# main-board-rev1d.net
KiCad netlist of a schematic drawn in EAGLE
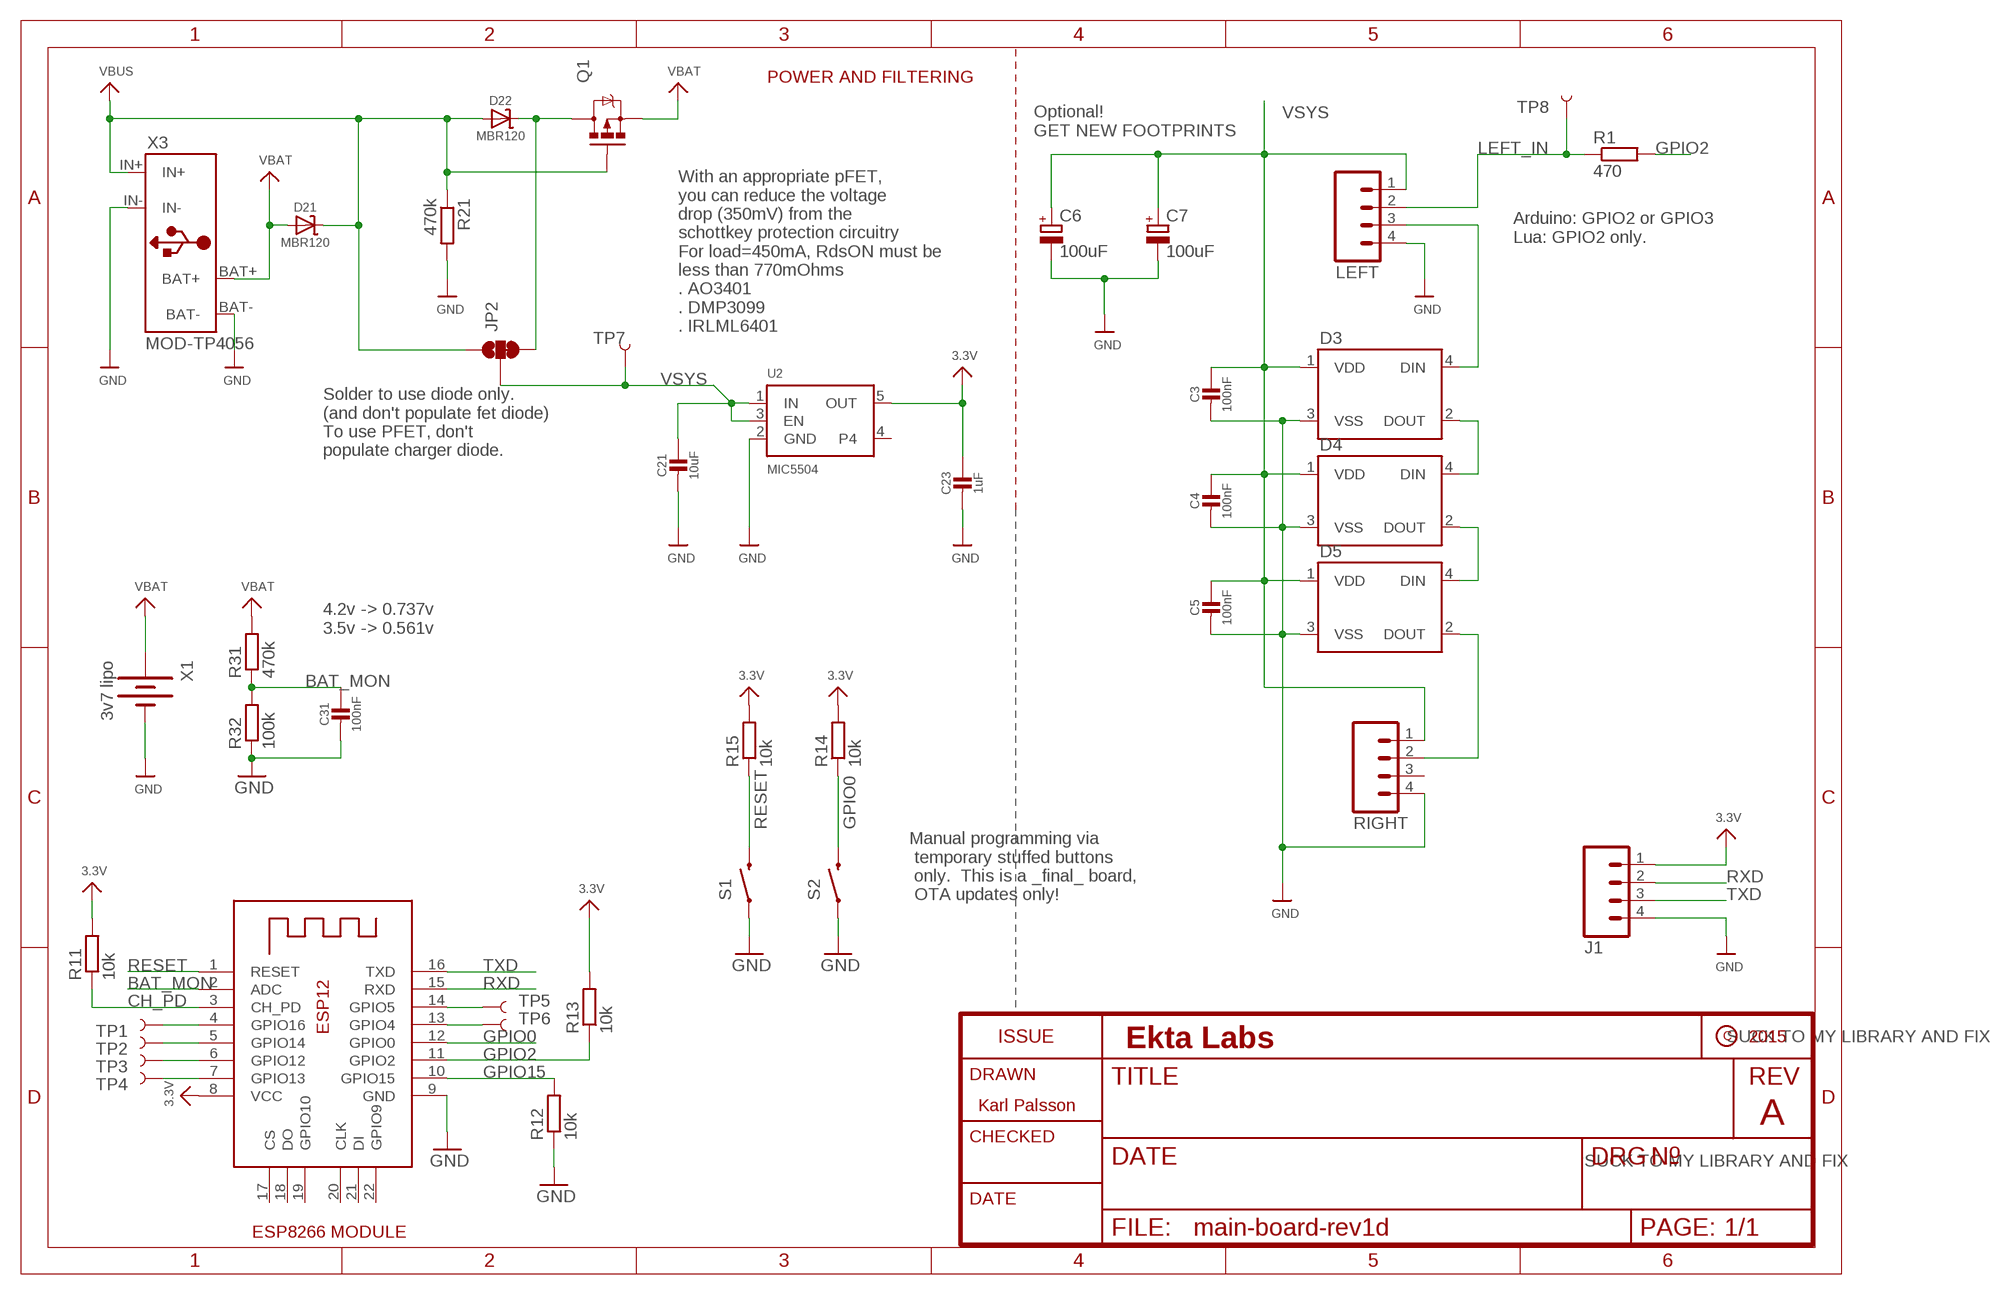
[diagram p0: schematic, sheet 1]

(export (version "E")
  (design (tool "Eeschema 10.0.6"))
  (components
    (comp (ref "C3")
      (value "100nF")
      (footprint "eagle-import:0805-NO")
      (libsource (lib "eagle-import") (part "CAP_CERAMIC0805-NOOUTLINE"))
    )
    (comp (ref "C4")
      (value "100nF")
      (footprint "eagle-import:0805-NO")
      (libsource (lib "eagle-import") (part "CAP_CERAMIC0805-NOOUTLINE"))
    )
    (comp (ref "C5")
      (value "100nF")
      (footprint "eagle-import:0805-NO")
      (libsource (lib "eagle-import") (part "CAP_CERAMIC0805-NOOUTLINE"))
    )
    (comp (ref "C6")
      (value "100uF")
      (footprint "eagle-import:PANASONIC_B")
      (libsource (lib "eagle-import") (part "CPOL-EUB"))
    )
    (comp (ref "C7")
      (value "100uF")
      (footprint "eagle-import:PANASONIC_B")
      (libsource (lib "eagle-import") (part "CPOL-EUB"))
    )
    (comp (ref "C21")
      (value "10uF")
      (footprint "eagle-import:0805-NO")
      (libsource (lib "eagle-import") (part "CAP_CERAMIC0805-NOOUTLINE"))
    )
    (comp (ref "C23")
      (value "1uF")
      (footprint "eagle-import:0805-NO")
      (libsource (lib "eagle-import") (part "CAP_CERAMIC0805-NOOUTLINE"))
    )
    (comp (ref "C31")
      (value "100nF")
      (footprint "eagle-import:0805-NO")
      (libsource (lib "eagle-import") (part "CAP_CERAMIC0805-NOOUTLINE"))
    )
    (comp (ref "D3")
      (value "WS2812B")
      (footprint "eagle-import:WS2812B")
      (libsource (lib "eagle-import") (part "WS2812B"))
    )
    (comp (ref "D4")
      (value "WS2812B")
      (footprint "eagle-import:WS2812B")
      (libsource (lib "eagle-import") (part "WS2812B"))
    )
    (comp (ref "D5")
      (value "WS2812B")
      (footprint "eagle-import:WS2812B")
      (libsource (lib "eagle-import") (part "WS2812B"))
    )
    (comp (ref "D21")
      (value "MBR120")
      (footprint "eagle-import:SOD-123")
      (libsource (lib "eagle-import") (part "DIODE-SCHOTTKYSOD-123"))
    )
    (comp (ref "D22")
      (value "MBR120")
      (footprint "eagle-import:SOD-123")
      (libsource (lib "eagle-import") (part "DIODE-SCHOTTKYSOD-123"))
    )
    (comp (ref "J1")
      (value "M041X04_NO_SILK")
      (footprint "eagle-import:1X04_NO_SILK")
      (libsource (lib "eagle-import") (part "M041X04_NO_SILK"))
    )
    (comp (ref "JP2")
      (value "JUMPER-PAD-3-2OF3_NC_BY_TRACE_LARGE")
      (footprint "eagle-import:PAD-JUMPER-3-2OF3_NC_BY_TRACE_YES_SILK_LARGE")
      (libsource (lib "eagle-import") (part "JUMPER-PAD-3-2OF3_NC_BY_TRACE_LARGE"))
    )
    (comp (ref "LEFT")
      (value "M041X04_NO_SILK")
      (footprint "eagle-import:1X04_NO_SILK")
      (libsource (lib "eagle-import") (part "M041X04_NO_SILK"))
    )
    (comp (ref "Q1")
      (value "MOSFET-PCHANNEL")
      (footprint "eagle-import:SOT23-3")
      (libsource (lib "eagle-import") (part "MOSFET-PCHANNEL"))
    )
    (comp (ref "R1")
      (value "470")
      (footprint "eagle-import:R0603")
      (libsource (lib "eagle-import") (part "R-EU_R0603"))
    )
    (comp (ref "R11")
      (value "10k")
      (footprint "eagle-import:R0603")
      (libsource (lib "eagle-import") (part "R-EU_R0603"))
    )
    (comp (ref "R12")
      (value "10k")
      (footprint "eagle-import:R0603")
      (libsource (lib "eagle-import") (part "R-EU_R0603"))
    )
    (comp (ref "R13")
      (value "10k")
      (footprint "eagle-import:R0603")
      (libsource (lib "eagle-import") (part "R-EU_R0603"))
    )
    (comp (ref "R14")
      (value "10k")
      (footprint "eagle-import:R0603")
      (libsource (lib "eagle-import") (part "R-EU_R0603"))
    )
    (comp (ref "R15")
      (value "10k")
      (footprint "eagle-import:R0603")
      (libsource (lib "eagle-import") (part "R-EU_R0603"))
    )
    (comp (ref "R21")
      (value "470k")
      (footprint "eagle-import:R0603")
      (libsource (lib "eagle-import") (part "R-EU_R0603"))
    )
    (comp (ref "R31")
      (value "470k")
      (footprint "eagle-import:R0603")
      (libsource (lib "eagle-import") (part "R-EU_R0603"))
    )
    (comp (ref "R32")
      (value "100k")
      (footprint "eagle-import:R0603")
      (libsource (lib "eagle-import") (part "R-EU_R0603"))
    )
    (comp (ref "RIGHT")
      (value "M041X04_NO_SILK")
      (footprint "eagle-import:1X04_NO_SILK")
      (libsource (lib "eagle-import") (part "M041X04_NO_SILK"))
    )
    (comp (ref "S1")
      (value "SWITCH-MOMENTARY-2PTH")
      (footprint "eagle-import:TACTILE-PTH")
      (libsource (lib "eagle-import") (part "SWITCH-MOMENTARY-2PTH"))
    )
    (comp (ref "S2")
      (value "SWITCH-MOMENTARY-2PTH")
      (footprint "eagle-import:TACTILE-PTH")
      (libsource (lib "eagle-import") (part "SWITCH-MOMENTARY-2PTH"))
    )
    (comp (ref "TP1")
      (value "TEST-POINTTP_06_TH")
      (footprint "eagle-import:TP_06TH")
      (libsource (lib "eagle-import") (part "TEST-POINTTP_06_TH"))
    )
    (comp (ref "TP2")
      (value "TEST-POINTTP_06_TH")
      (footprint "eagle-import:TP_06TH")
      (libsource (lib "eagle-import") (part "TEST-POINTTP_06_TH"))
    )
    (comp (ref "TP3")
      (value "TEST-POINTTP_06_TH")
      (footprint "eagle-import:TP_06TH")
      (libsource (lib "eagle-import") (part "TEST-POINTTP_06_TH"))
    )
    (comp (ref "TP4")
      (value "TEST-POINTTP_06_TH")
      (footprint "eagle-import:TP_06TH")
      (libsource (lib "eagle-import") (part "TEST-POINTTP_06_TH"))
    )
    (comp (ref "TP5")
      (value "TEST-POINTTP_06_TH")
      (footprint "eagle-import:TP_06TH")
      (libsource (lib "eagle-import") (part "TEST-POINTTP_06_TH"))
    )
    (comp (ref "TP6")
      (value "TEST-POINTTP_06_TH")
      (footprint "eagle-import:TP_06TH")
      (libsource (lib "eagle-import") (part "TEST-POINTTP_06_TH"))
    )
    (comp (ref "TP7")
      (value "TEST-POINTTP_06_TH")
      (footprint "eagle-import:TP_06TH")
      (libsource (lib "eagle-import") (part "TEST-POINTTP_06_TH"))
    )
    (comp (ref "TP8")
      (value "TEST-POINTTP_06_TH")
      (footprint "eagle-import:TP_06TH")
      (libsource (lib "eagle-import") (part "TEST-POINTTP_06_TH"))
    )
    (comp (ref "U2")
      (value "MIC5504")
      (footprint "eagle-import:SOT23-5")
      (libsource (lib "eagle-import") (part "VREG_SOT23-5"))
    )
    (comp (ref "X1")
      (value "3v7 lipo")
      (footprint "eagle-import:BATT-18650-BLOSSOM-1")
      (libsource (lib "eagle-import") (part "BATTERY18650-BLOSSOM"))
    )
    (comp (ref "X2")
      (value "ESP-12")
      (footprint "eagle-import:ESP-12E")
      (libsource (lib "eagle-import") (part "ESP-12E"))
    )
    (comp (ref "X3")
      (value "MOD-TP4056")
      (footprint "eagle-import:MOD-LIPO_CHARGER")
      (libsource (lib "eagle-import") (part "MOD-LIPO_CHARGER"))
    )
  )
  (nets
    (net (code "1") (name "/BAT_MON") (class "Default")
      (node (ref "C31") (pin "1") (pinfunction "1_1") (pintype "passive"))
      (node (ref "R31") (pin "1") (pinfunction "1_1") (pintype "passive"))
      (node (ref "R32") (pin "2") (pinfunction "2_2") (pintype "passive"))
      (node (ref "X2") (pin "2") (pinfunction "ADC_2") (pintype "passive"))
    )
    (net (code "2") (name "/CH_PD") (class "Default")
      (node (ref "R11") (pin "1") (pinfunction "1_1") (pintype "passive"))
      (node (ref "X2") (pin "3") (pinfunction "CH_PD_3") (pintype "input"))
    )
    (net (code "3") (name "/GPIO0") (class "Default")
      (node (ref "R14") (pin "1") (pinfunction "1_1") (pintype "passive"))
      (node (ref "S2") (pin "3") (pinfunction "2_3") (pintype "passive"))
      (node (ref "X2") (pin "12") (pinfunction "GPIO0_12") (pintype "bidirectional"))
    )
    (net (code "4") (name "/GPIO2") (class "Default")
      (node (ref "R1") (pin "2") (pinfunction "2_2") (pintype "passive"))
      (node (ref "R13") (pin "1") (pinfunction "1_1") (pintype "passive"))
      (node (ref "X2") (pin "11") (pinfunction "GPIO2_11") (pintype "bidirectional"))
    )
    (net (code "5") (name "/GPIO15") (class "Default")
      (node (ref "R12") (pin "2") (pinfunction "2_2") (pintype "passive"))
      (node (ref "X2") (pin "10") (pinfunction "GPIO15_10") (pintype "bidirectional"))
    )
    (net (code "6") (name "/LEFT_IN") (class "Default")
      (node (ref "LEFT") (pin "2") (pinfunction "2_2") (pintype "passive"))
      (node (ref "R1") (pin "1") (pinfunction "1_1") (pintype "passive"))
      (node (ref "TP8") (pin "P$1") (pinfunction "1_P$1") (pintype "bidirectional"))
    )
    (net (code "7") (name "/RESET") (class "Default")
      (node (ref "R15") (pin "1") (pinfunction "1_1") (pintype "passive"))
      (node (ref "S1") (pin "3") (pinfunction "2_3") (pintype "passive"))
      (node (ref "X2") (pin "1") (pinfunction "RESET_1") (pintype "input"))
    )
    (net (code "8") (name "/RXD") (class "Default")
      (node (ref "J1") (pin "2") (pinfunction "2_2") (pintype "passive"))
      (node (ref "X2") (pin "15") (pinfunction "RXD_15") (pintype "input"))
    )
    (net (code "9") (name "/TXD") (class "Default")
      (node (ref "J1") (pin "3") (pinfunction "3_3") (pintype "passive"))
      (node (ref "X2") (pin "16") (pinfunction "TXD_16") (pintype "output"))
    )
    (net (code "10") (name "/VSYS") (class "Default")
      (node (ref "C21") (pin "1") (pinfunction "1_1") (pintype "passive"))
      (node (ref "C3") (pin "1") (pinfunction "1_1") (pintype "passive"))
      (node (ref "C4") (pin "1") (pinfunction "1_1") (pintype "passive"))
      (node (ref "C5") (pin "1") (pinfunction "1_1") (pintype "passive"))
      (node (ref "C6") (pin "+") (pinfunction "+_+") (pintype "passive"))
      (node (ref "C7") (pin "+") (pinfunction "+_+") (pintype "passive"))
      (node (ref "D3") (pin "1") (pinfunction "VDD_1") (pintype "power_in"))
      (node (ref "D4") (pin "1") (pinfunction "VDD_1") (pintype "power_in"))
      (node (ref "D5") (pin "1") (pinfunction "VDD_1") (pintype "power_in"))
      (node (ref "JP2") (pin "2") (pinfunction "2_2") (pintype "passive"))
      (node (ref "LEFT") (pin "1") (pinfunction "1_1") (pintype "passive"))
      (node (ref "RIGHT") (pin "1") (pinfunction "1_1") (pintype "passive"))
      (node (ref "TP7") (pin "P$1") (pinfunction "1_P$1") (pintype "bidirectional"))
      (node (ref "U2") (pin "1") (pinfunction "IN_1") (pintype "power_in"))
      (node (ref "U2") (pin "3") (pinfunction "EN_3") (pintype "input"))
    )
    (net (code "11") (name "3.3V") (class "Default")
      (node (ref "C23") (pin "1") (pinfunction "1_1") (pintype "passive"))
      (node (ref "J1") (pin "1") (pinfunction "1_1") (pintype "passive"))
      (node (ref "R11") (pin "2") (pinfunction "2_2") (pintype "passive"))
      (node (ref "R13") (pin "2") (pinfunction "2_2") (pintype "passive"))
      (node (ref "R14") (pin "2") (pinfunction "2_2") (pintype "passive"))
      (node (ref "R15") (pin "2") (pinfunction "2_2") (pintype "passive"))
      (node (ref "U2") (pin "5") (pinfunction "OUT_5") (pintype "power_in"))
      (node (ref "X2") (pin "8") (pinfunction "VCC_8") (pintype "power_in"))
    )
    (net (code "12") (name "GND") (class "Default")
      (node (ref "C21") (pin "2") (pinfunction "2_2") (pintype "passive"))
      (node (ref "C23") (pin "2") (pinfunction "2_2") (pintype "passive"))
      (node (ref "C3") (pin "2") (pinfunction "2_2") (pintype "passive"))
      (node (ref "C31") (pin "2") (pinfunction "2_2") (pintype "passive"))
      (node (ref "C4") (pin "2") (pinfunction "2_2") (pintype "passive"))
      (node (ref "C5") (pin "2") (pinfunction "2_2") (pintype "passive"))
      (node (ref "C6") (pin "-") (pinfunction "-_-") (pintype "passive"))
      (node (ref "C7") (pin "-") (pinfunction "-_-") (pintype "passive"))
      (node (ref "D3") (pin "3") (pinfunction "VSS_3") (pintype "power_in"))
      (node (ref "D4") (pin "3") (pinfunction "VSS_3") (pintype "power_in"))
      (node (ref "D5") (pin "3") (pinfunction "VSS_3") (pintype "power_in"))
      (node (ref "J1") (pin "4") (pinfunction "4_4") (pintype "passive"))
      (node (ref "LEFT") (pin "4") (pinfunction "4_4") (pintype "passive"))
      (node (ref "R12") (pin "1") (pinfunction "1_1") (pintype "passive"))
      (node (ref "R21") (pin "2") (pinfunction "2_2") (pintype "passive"))
      (node (ref "R32") (pin "1") (pinfunction "1_1") (pintype "passive"))
      (node (ref "RIGHT") (pin "4") (pinfunction "4_4") (pintype "passive"))
      (node (ref "S1") (pin "1") (pinfunction "1_1") (pintype "passive"))
      (node (ref "S2") (pin "1") (pinfunction "1_1") (pintype "passive"))
      (node (ref "U2") (pin "2") (pinfunction "GND_2") (pintype "power_in"))
      (node (ref "X1") (pin "-") (pinfunction "-_-") (pintype "power_in"))
      (node (ref "X2") (pin "9") (pinfunction "GND_9") (pintype "power_in"))
      (node (ref "X3") (pin "BAT-") (pinfunction "BAT-_BAT-") (pintype "bidirectional"))
      (node (ref "X3") (pin "IN-") (pinfunction "IN-_IN-") (pintype "bidirectional"))
    )
    (net (code "13") (name "Net-(D3-DIN)") (class "Default")
      (node (ref "D3") (pin "4") (pinfunction "DIN_4") (pintype "input"))
      (node (ref "LEFT") (pin "3") (pinfunction "3_3") (pintype "passive"))
    )
    (net (code "14") (name "Net-(D3-DOUT)") (class "Default")
      (node (ref "D3") (pin "2") (pinfunction "DOUT_2") (pintype "output"))
      (node (ref "D4") (pin "4") (pinfunction "DIN_4") (pintype "input"))
    )
    (net (code "15") (name "Net-(D4-DOUT)") (class "Default")
      (node (ref "D4") (pin "2") (pinfunction "DOUT_2") (pintype "output"))
      (node (ref "D5") (pin "4") (pinfunction "DIN_4") (pintype "input"))
    )
    (net (code "16") (name "Net-(D5-DOUT)") (class "Default")
      (node (ref "D5") (pin "2") (pinfunction "DOUT_2") (pintype "output"))
      (node (ref "RIGHT") (pin "2") (pinfunction "2_2") (pintype "passive"))
    )
    (net (code "17") (name "Net-(Q1-D)") (class "Default")
      (node (ref "D22") (pin "C") (pinfunction "C_C") (pintype "passive"))
      (node (ref "JP2") (pin "3") (pinfunction "3_3") (pintype "passive"))
      (node (ref "Q1") (pin "3") (pinfunction "D_3") (pintype "passive"))
    )
    (net (code "18") (name "Net-(TP1-1)") (class "Default")
      (node (ref "TP1") (pin "P$1") (pinfunction "1_P$1") (pintype "bidirectional"))
      (node (ref "X2") (pin "4") (pinfunction "GPIO16_4") (pintype "bidirectional"))
    )
    (net (code "19") (name "Net-(TP2-1)") (class "Default")
      (node (ref "TP2") (pin "P$1") (pinfunction "1_P$1") (pintype "bidirectional"))
      (node (ref "X2") (pin "5") (pinfunction "GPIO14_5") (pintype "bidirectional"))
    )
    (net (code "20") (name "Net-(TP3-1)") (class "Default")
      (node (ref "TP3") (pin "P$1") (pinfunction "1_P$1") (pintype "bidirectional"))
      (node (ref "X2") (pin "6") (pinfunction "GPIO12_6") (pintype "bidirectional"))
    )
    (net (code "21") (name "Net-(TP4-1)") (class "Default")
      (node (ref "TP4") (pin "P$1") (pinfunction "1_P$1") (pintype "bidirectional"))
      (node (ref "X2") (pin "7") (pinfunction "GPIO13_7") (pintype "bidirectional"))
    )
    (net (code "22") (name "Net-(TP5-1)") (class "Default")
      (node (ref "TP5") (pin "P$1") (pinfunction "1_P$1") (pintype "bidirectional"))
      (node (ref "X2") (pin "14") (pinfunction "GPIO5_14") (pintype "bidirectional"))
    )
    (net (code "23") (name "Net-(TP6-1)") (class "Default")
      (node (ref "TP6") (pin "P$1") (pinfunction "1_P$1") (pintype "bidirectional"))
      (node (ref "X2") (pin "13") (pinfunction "GPIO4_13") (pintype "bidirectional"))
    )
    (net (code "24") (name "VBAT") (class "Default")
      (node (ref "D21") (pin "A") (pinfunction "A_A") (pintype "passive"))
      (node (ref "Q1") (pin "2") (pinfunction "S_2") (pintype "passive"))
      (node (ref "R31") (pin "2") (pinfunction "2_2") (pintype "passive"))
      (node (ref "X1") (pin "+") (pinfunction "+_+") (pintype "power_in"))
      (node (ref "X3") (pin "BAT+") (pinfunction "BAT+_BAT+") (pintype "bidirectional"))
    )
    (net (code "25") (name "VBUS") (class "Default")
      (node (ref "D21") (pin "C") (pinfunction "C_C") (pintype "passive"))
      (node (ref "D22") (pin "A") (pinfunction "A_A") (pintype "passive"))
      (node (ref "JP2") (pin "1") (pinfunction "1_1") (pintype "passive"))
      (node (ref "Q1") (pin "1") (pinfunction "G_1") (pintype "passive"))
      (node (ref "R21") (pin "1") (pinfunction "1_1") (pintype "passive"))
      (node (ref "X3") (pin "IN+") (pinfunction "IN+_IN+") (pintype "bidirectional"))
    )
    (net (code "26") (name "unconnected-(RIGHT-Pad3)") (class "Default")
      (node (ref "RIGHT") (pin "3") (pinfunction "3_3") (pintype "passive"))
    )
    (net (code "27") (name "unconnected-(U2-P4-Pad4)") (class "Default")
      (node (ref "U2") (pin "4") (pinfunction "P4_4") (pintype "bidirectional"))
    )
    (net (code "28") (name "unconnected-(X2-CLK-Pad20)") (class "Default")
      (node (ref "X2") (pin "20") (pinfunction "CLK_20") (pintype "bidirectional"))
    )
    (net (code "29") (name "unconnected-(X2-CS-Pad17)") (class "Default")
      (node (ref "X2") (pin "17") (pinfunction "CS_17") (pintype "bidirectional"))
    )
    (net (code "30") (name "unconnected-(X2-DI-Pad21)") (class "Default")
      (node (ref "X2") (pin "21") (pinfunction "DI_21") (pintype "bidirectional"))
    )
    (net (code "31") (name "unconnected-(X2-DO-Pad18)") (class "Default")
      (node (ref "X2") (pin "18") (pinfunction "DO_18") (pintype "bidirectional"))
    )
    (net (code "32") (name "unconnected-(X2-GPIO9-Pad22)") (class "Default")
      (node (ref "X2") (pin "22") (pinfunction "GPIO9_22") (pintype "bidirectional"))
    )
    (net (code "33") (name "unconnected-(X2-GPIO10-Pad19)") (class "Default")
      (node (ref "X2") (pin "19") (pinfunction "GPIO10_19") (pintype "bidirectional"))
    )
  )
)
